# PCB_DYBoard_FlexiFlex.net
KiCad netlist of a schematic drawn in Altium Designer
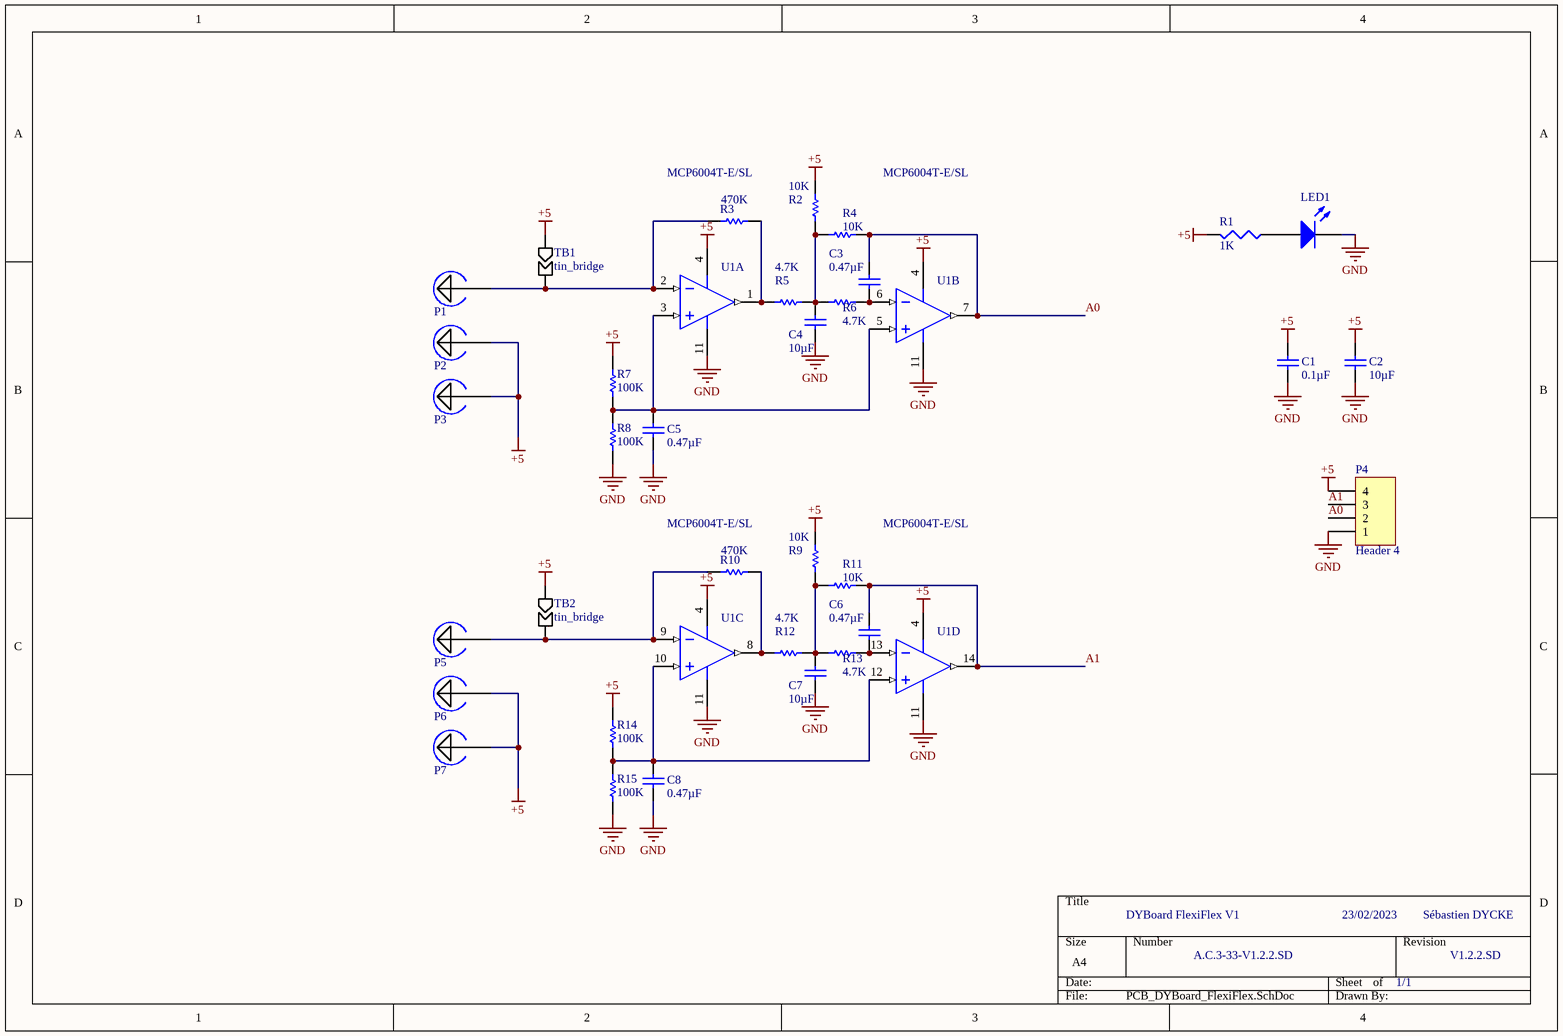
[diagram p0: PCB_DYBoard_FlexiFlex.SchDoc]

(export (version "E")
  (design (tool "Eeschema 10.0.6"))
  (components
    (comp (ref "C1")
      (value "0.1µF")
      (footprint "1608[0603]")
      (description "Capacitor (Semiconductor SIM Model)")
      (fields (field (name "Comment") "Cap Semi") (field (name "PUBLISHER") "Altium Limited"))
      (libsource (lib "Miscellaneous Devices") (part "Cap Semi"))
    )
    (comp (ref "C2")
      (value "10µF")
      (footprint "1608[0603]")
      (description "Capacitor (Semiconductor SIM Model)")
      (fields (field (name "Comment") "Cap Semi") (field (name "PUBLISHER") "Altium Limited"))
      (libsource (lib "Miscellaneous Devices") (part "Cap Semi"))
    )
    (comp (ref "C3")
      (value "0.47µF")
      (footprint "1608[0603]")
      (description "Capacitor (Semiconductor SIM Model)")
      (fields (field (name "Comment") "Cap Semi") (field (name "PUBLISHER") "Altium Limited"))
      (libsource (lib "Miscellaneous Devices") (part "Cap Semi"))
    )
    (comp (ref "C4")
      (value "10µF")
      (footprint "1608[0603]")
      (description "Capacitor (Semiconductor SIM Model)")
      (fields (field (name "Comment") "Cap Semi") (field (name "PUBLISHER") "Altium Limited"))
      (libsource (lib "Miscellaneous Devices") (part "Cap Semi"))
    )
    (comp (ref "C5")
      (value "0.47µF")
      (footprint "1608[0603]")
      (description "Capacitor (Semiconductor SIM Model)")
      (fields (field (name "Comment") "Cap Semi") (field (name "PUBLISHER") "Altium Limited"))
      (libsource (lib "Miscellaneous Devices") (part "Cap Semi"))
    )
    (comp (ref "C6")
      (value "0.47µF")
      (footprint "1608[0603]")
      (description "Capacitor (Semiconductor SIM Model)")
      (fields (field (name "Comment") "Cap Semi") (field (name "PUBLISHER") "Altium Limited"))
      (libsource (lib "Miscellaneous Devices") (part "Cap Semi"))
    )
    (comp (ref "C7")
      (value "10µF")
      (footprint "1608[0603]")
      (description "Capacitor (Semiconductor SIM Model)")
      (fields (field (name "Comment") "Cap Semi") (field (name "PUBLISHER") "Altium Limited"))
      (libsource (lib "Miscellaneous Devices") (part "Cap Semi"))
    )
    (comp (ref "C8")
      (value "0.47µF")
      (footprint "1608[0603]")
      (description "Capacitor (Semiconductor SIM Model)")
      (fields (field (name "Comment") "Cap Semi") (field (name "PUBLISHER") "Altium Limited"))
      (libsource (lib "Miscellaneous Devices") (part "Cap Semi"))
    )
    (comp (ref "LED1")
      (value "150060BS75000")
      (footprint "0603_A")
      (description "SMD mono-color Chip LED, WL-SMCW, Blue")
      (fields (field (name "MANUFACTURER") "Wuerth Elektronik"))
      (libsource (lib "Altium Content Vault") (part "WE-LED_K1A2-2"))
    )
    (comp (ref "P1")
      (value "solderPad")
      (footprint "solderPad")
      (libsource (lib "Lib_Altium_Sebastien_DYCKE") (part "solderPad"))
    )
    (comp (ref "P2")
      (value "solderPad")
      (footprint "solderPad")
      (libsource (lib "Lib_Altium_Sebastien_DYCKE") (part "solderPad"))
    )
    (comp (ref "P3")
      (value "solderPad")
      (footprint "solderPad")
      (libsource (lib "Lib_Altium_Sebastien_DYCKE") (part "solderPad"))
    )
    (comp (ref "P4")
      (value "Header 4")
      (footprint "HDR1X4")
      (description "Header, 4-Pin")
      (fields (field (name "PUBLISHER") "Altium Limited"))
      (libsource (lib "Miscellaneous Connectors") (part "Header 4"))
    )
    (comp (ref "P5")
      (value "solderPad")
      (footprint "solderPad")
      (libsource (lib "Lib_Altium_Sebastien_DYCKE") (part "solderPad"))
    )
    (comp (ref "P6")
      (value "solderPad")
      (footprint "solderPad")
      (libsource (lib "Lib_Altium_Sebastien_DYCKE") (part "solderPad"))
    )
    (comp (ref "P7")
      (value "solderPad")
      (footprint "solderPad")
      (libsource (lib "Lib_Altium_Sebastien_DYCKE") (part "solderPad"))
    )
    (comp (ref "R1")
      (value "1K")
      (footprint "J1-0603")
      (description "Resistor")
      (fields (field (name "Comment") "Res3") (field (name "PUBLISHER") "Altium Limited"))
      (libsource (lib "Miscellaneous Devices") (part "Res3"))
    )
    (comp (ref "R2")
      (value "10K")
      (footprint "RESC1609X60X30LL10T20")
      (fields (field (name "PART NUMBER") "RCWE0603R560FKEA") (field (name "MANUFACTURER") "Vishay Dale"))
      (libsource (lib "Altium Content Vault") (part "RES"))
    )
    (comp (ref "R3")
      (value "470K")
      (footprint "RESC1609X60X30LL10T20")
      (fields (field (name "PART NUMBER") "RCWE0603R560FKEA") (field (name "MANUFACTURER") "Vishay Dale"))
      (libsource (lib "Altium Content Vault") (part "RES"))
    )
    (comp (ref "R4")
      (value "10K")
      (footprint "RESC1609X60X30LL10T20")
      (fields (field (name "PART NUMBER") "RCWE0603R560FKEA") (field (name "MANUFACTURER") "Vishay Dale"))
      (libsource (lib "Altium Content Vault") (part "RES"))
    )
    (comp (ref "R5")
      (value "4.7K")
      (footprint "RESC1609X60X30LL10T20")
      (fields (field (name "PART NUMBER") "RCWE0603R560FKEA") (field (name "MANUFACTURER") "Vishay Dale"))
      (libsource (lib "Altium Content Vault") (part "RES"))
    )
    (comp (ref "R6")
      (value "4.7K")
      (footprint "RESC1609X60X30LL10T20")
      (fields (field (name "PART NUMBER") "RCWE0603R560FKEA") (field (name "MANUFACTURER") "Vishay Dale"))
      (libsource (lib "Altium Content Vault") (part "RES"))
    )
    (comp (ref "R7")
      (value "100K")
      (footprint "RESC1609X60X30LL10T20")
      (fields (field (name "PART NUMBER") "RCWE0603R560FKEA") (field (name "MANUFACTURER") "Vishay Dale"))
      (libsource (lib "Altium Content Vault") (part "RES"))
    )
    (comp (ref "R8")
      (value "100K")
      (footprint "RESC1609X60X30LL10T20")
      (fields (field (name "PART NUMBER") "RCWE0603R560FKEA") (field (name "MANUFACTURER") "Vishay Dale"))
      (libsource (lib "Altium Content Vault") (part "RES"))
    )
    (comp (ref "R9")
      (value "10K")
      (footprint "RESC1609X60X30LL10T20")
      (fields (field (name "PART NUMBER") "RCWE0603R560FKEA") (field (name "MANUFACTURER") "Vishay Dale"))
      (libsource (lib "Altium Content Vault") (part "RES"))
    )
    (comp (ref "R10")
      (value "470K")
      (footprint "RESC1609X60X30LL10T20")
      (fields (field (name "PART NUMBER") "RCWE0603R560FKEA") (field (name "MANUFACTURER") "Vishay Dale"))
      (libsource (lib "Altium Content Vault") (part "RES"))
    )
    (comp (ref "R11")
      (value "10K")
      (footprint "RESC1609X60X30LL10T20")
      (fields (field (name "PART NUMBER") "RCWE0603R560FKEA") (field (name "MANUFACTURER") "Vishay Dale"))
      (libsource (lib "Altium Content Vault") (part "RES"))
    )
    (comp (ref "R12")
      (value "4.7K")
      (footprint "RESC1609X60X30LL10T20")
      (fields (field (name "PART NUMBER") "RCWE0603R560FKEA") (field (name "MANUFACTURER") "Vishay Dale"))
      (libsource (lib "Altium Content Vault") (part "RES"))
    )
    (comp (ref "R13")
      (value "4.7K")
      (footprint "RESC1609X60X30LL10T20")
      (fields (field (name "PART NUMBER") "RCWE0603R560FKEA") (field (name "MANUFACTURER") "Vishay Dale"))
      (libsource (lib "Altium Content Vault") (part "RES"))
    )
    (comp (ref "R14")
      (value "100K")
      (footprint "RESC1609X60X30LL10T20")
      (fields (field (name "PART NUMBER") "RCWE0603R560FKEA") (field (name "MANUFACTURER") "Vishay Dale"))
      (libsource (lib "Altium Content Vault") (part "RES"))
    )
    (comp (ref "R15")
      (value "100K")
      (footprint "RESC1609X60X30LL10T20")
      (fields (field (name "PART NUMBER") "RCWE0603R560FKEA") (field (name "MANUFACTURER") "Vishay Dale"))
      (libsource (lib "Altium Content Vault") (part "RES"))
    )
    (comp (ref "TB1")
      (value "tin_bridge")
      (footprint "tin_bridge")
      (libsource (lib "Lib_Altium_Sebastien_DYCKE") (part "tin_bridge"))
    )
    (comp (ref "TB2")
      (value "tin_bridge")
      (footprint "tin_bridge")
      (libsource (lib "Lib_Altium_Sebastien_DYCKE") (part "tin_bridge"))
    )
    (comp (ref "U1")
      (value "MCP6004T-E/SL")
      (footprint "SOIC-SL14_M")
      (description "None")
      (libsource (lib "Altium Content Vault") (part "AMP-OPA-MCP6004-IL14"))
    )
  )
  (nets
    (net (code "1") (name "+5") (class "Default")
      (node (ref "C1") (pin "2") (pinfunction "2_2") (pintype "passive"))
      (node (ref "C2") (pin "2") (pinfunction "2_2") (pintype "passive"))
      (node (ref "P2") (pin "20") (pinfunction "20_20") (pintype "passive"))
      (node (ref "P3") (pin "20") (pinfunction "20_20") (pintype "passive"))
      (node (ref "P4") (pin "4") (pinfunction "4_4") (pintype "passive"))
      (node (ref "P6") (pin "20") (pinfunction "20_20") (pintype "passive"))
      (node (ref "P7") (pin "20") (pinfunction "20_20") (pintype "passive"))
      (node (ref "R1") (pin "2") (pinfunction "2_2") (pintype "passive"))
      (node (ref "R14") (pin "1") (pinfunction "1_1") (pintype "passive"))
      (node (ref "R2") (pin "1") (pinfunction "1_1") (pintype "passive"))
      (node (ref "R7") (pin "1") (pinfunction "1_1") (pintype "passive"))
      (node (ref "R9") (pin "1") (pinfunction "1_1") (pintype "passive"))
      (node (ref "TB1") (pin "21") (pinfunction "21_21") (pintype "passive"))
      (node (ref "TB2") (pin "21") (pinfunction "21_21") (pintype "passive"))
      (node (ref "U1") (pin "4") (pinfunction "VDD_4") (pintype "power_in"))
    )
    (net (code "2") (name "/A0") (class "Default")
      (node (ref "C3") (pin "2") (pinfunction "2_2") (pintype "passive"))
      (node (ref "P4") (pin "2") (pinfunction "2_2") (pintype "passive"))
      (node (ref "R4") (pin "1") (pinfunction "1_1") (pintype "passive"))
      (node (ref "U1") (pin "7") (pinfunction "VOUTB_7") (pintype "output"))
    )
    (net (code "3") (name "/A1") (class "Default")
      (node (ref "C6") (pin "2") (pinfunction "2_2") (pintype "passive"))
      (node (ref "P4") (pin "3") (pinfunction "3_3") (pintype "passive"))
      (node (ref "R11") (pin "1") (pinfunction "1_1") (pintype "passive"))
      (node (ref "U1") (pin "14") (pinfunction "VOUTD_14") (pintype "output"))
    )
    (net (code "4") (name "GND") (class "Default")
      (node (ref "C1") (pin "1") (pinfunction "1_1") (pintype "passive"))
      (node (ref "C2") (pin "1") (pinfunction "1_1") (pintype "passive"))
      (node (ref "C4") (pin "2") (pinfunction "2_2") (pintype "passive"))
      (node (ref "C5") (pin "1") (pinfunction "1_1") (pintype "passive"))
      (node (ref "C7") (pin "2") (pinfunction "2_2") (pintype "passive"))
      (node (ref "C8") (pin "1") (pinfunction "1_1") (pintype "passive"))
      (node (ref "LED1") (pin "1") (pinfunction "K_1") (pintype "passive"))
      (node (ref "P4") (pin "1") (pinfunction "1_1") (pintype "passive"))
      (node (ref "R15") (pin "2") (pinfunction "2_2") (pintype "passive"))
      (node (ref "R8") (pin "2") (pinfunction "2_2") (pintype "passive"))
      (node (ref "U1") (pin "11") (pinfunction "VSS_11") (pintype "power_in"))
    )
    (net (code "5") (name "Net-(C4-Pad1)") (class "Default")
      (node (ref "C4") (pin "1") (pinfunction "1_1") (pintype "passive"))
      (node (ref "R2") (pin "2") (pinfunction "2_2") (pintype "passive"))
      (node (ref "R4") (pin "2") (pinfunction "2_2") (pintype "passive"))
      (node (ref "R5") (pin "1") (pinfunction "1_1") (pintype "passive"))
      (node (ref "R6") (pin "2") (pinfunction "2_2") (pintype "passive"))
    )
    (net (code "6") (name "Net-(C7-Pad1)") (class "Default")
      (node (ref "C7") (pin "1") (pinfunction "1_1") (pintype "passive"))
      (node (ref "R11") (pin "2") (pinfunction "2_2") (pintype "passive"))
      (node (ref "R12") (pin "1") (pinfunction "1_1") (pintype "passive"))
      (node (ref "R13") (pin "2") (pinfunction "2_2") (pintype "passive"))
      (node (ref "R9") (pin "2") (pinfunction "2_2") (pintype "passive"))
    )
    (net (code "7") (name "Net-(LED1-A)") (class "Default")
      (node (ref "LED1") (pin "2") (pinfunction "A_2") (pintype "passive"))
      (node (ref "R1") (pin "1") (pinfunction "1_1") (pintype "passive"))
    )
    (net (code "8") (name "Net-(U1A-VINA+)") (class "Default")
      (node (ref "C5") (pin "2") (pinfunction "2_2") (pintype "passive"))
      (node (ref "R7") (pin "2") (pinfunction "2_2") (pintype "passive"))
      (node (ref "R8") (pin "1") (pinfunction "1_1") (pintype "passive"))
      (node (ref "U1") (pin "3") (pinfunction "VINA+_3") (pintype "input"))
      (node (ref "U1") (pin "5") (pinfunction "VINB+_5") (pintype "input"))
    )
    (net (code "9") (name "Net-(U1A-VINA-)") (class "Default")
      (node (ref "P1") (pin "20") (pinfunction "20_20") (pintype "passive"))
      (node (ref "R3") (pin "2") (pinfunction "2_2") (pintype "passive"))
      (node (ref "TB1") (pin "22") (pinfunction "22_22") (pintype "passive"))
      (node (ref "U1") (pin "2") (pinfunction "VINA-_2") (pintype "input"))
    )
    (net (code "10") (name "Net-(U1A-VOUTA)") (class "Default")
      (node (ref "R3") (pin "1") (pinfunction "1_1") (pintype "passive"))
      (node (ref "R5") (pin "2") (pinfunction "2_2") (pintype "passive"))
      (node (ref "U1") (pin "1") (pinfunction "VOUTA_1") (pintype "output"))
    )
    (net (code "11") (name "Net-(U1B-VINB-)") (class "Default")
      (node (ref "C3") (pin "1") (pinfunction "1_1") (pintype "passive"))
      (node (ref "R6") (pin "1") (pinfunction "1_1") (pintype "passive"))
      (node (ref "U1") (pin "6") (pinfunction "VINB-_6") (pintype "input"))
    )
    (net (code "12") (name "Net-(U1C-VINC+)") (class "Default")
      (node (ref "C8") (pin "2") (pinfunction "2_2") (pintype "passive"))
      (node (ref "R14") (pin "2") (pinfunction "2_2") (pintype "passive"))
      (node (ref "R15") (pin "1") (pinfunction "1_1") (pintype "passive"))
      (node (ref "U1") (pin "10") (pinfunction "VINC+_10") (pintype "input"))
      (node (ref "U1") (pin "12") (pinfunction "VIND+_12") (pintype "input"))
    )
    (net (code "13") (name "Net-(U1C-VINC-)") (class "Default")
      (node (ref "P5") (pin "20") (pinfunction "20_20") (pintype "passive"))
      (node (ref "R10") (pin "2") (pinfunction "2_2") (pintype "passive"))
      (node (ref "TB2") (pin "22") (pinfunction "22_22") (pintype "passive"))
      (node (ref "U1") (pin "9") (pinfunction "VINC-_9") (pintype "input"))
    )
    (net (code "14") (name "Net-(U1C-VOUTC)") (class "Default")
      (node (ref "R10") (pin "1") (pinfunction "1_1") (pintype "passive"))
      (node (ref "R12") (pin "2") (pinfunction "2_2") (pintype "passive"))
      (node (ref "U1") (pin "8") (pinfunction "VOUTC_8") (pintype "output"))
    )
    (net (code "15") (name "Net-(U1D-VIND-)") (class "Default")
      (node (ref "C6") (pin "1") (pinfunction "1_1") (pintype "passive"))
      (node (ref "R13") (pin "1") (pinfunction "1_1") (pintype "passive"))
      (node (ref "U1") (pin "13") (pinfunction "VIND-_13") (pintype "input"))
    )
  )
)
